# pcb.net
KiCad netlist of a schematic drawn in EAGLE
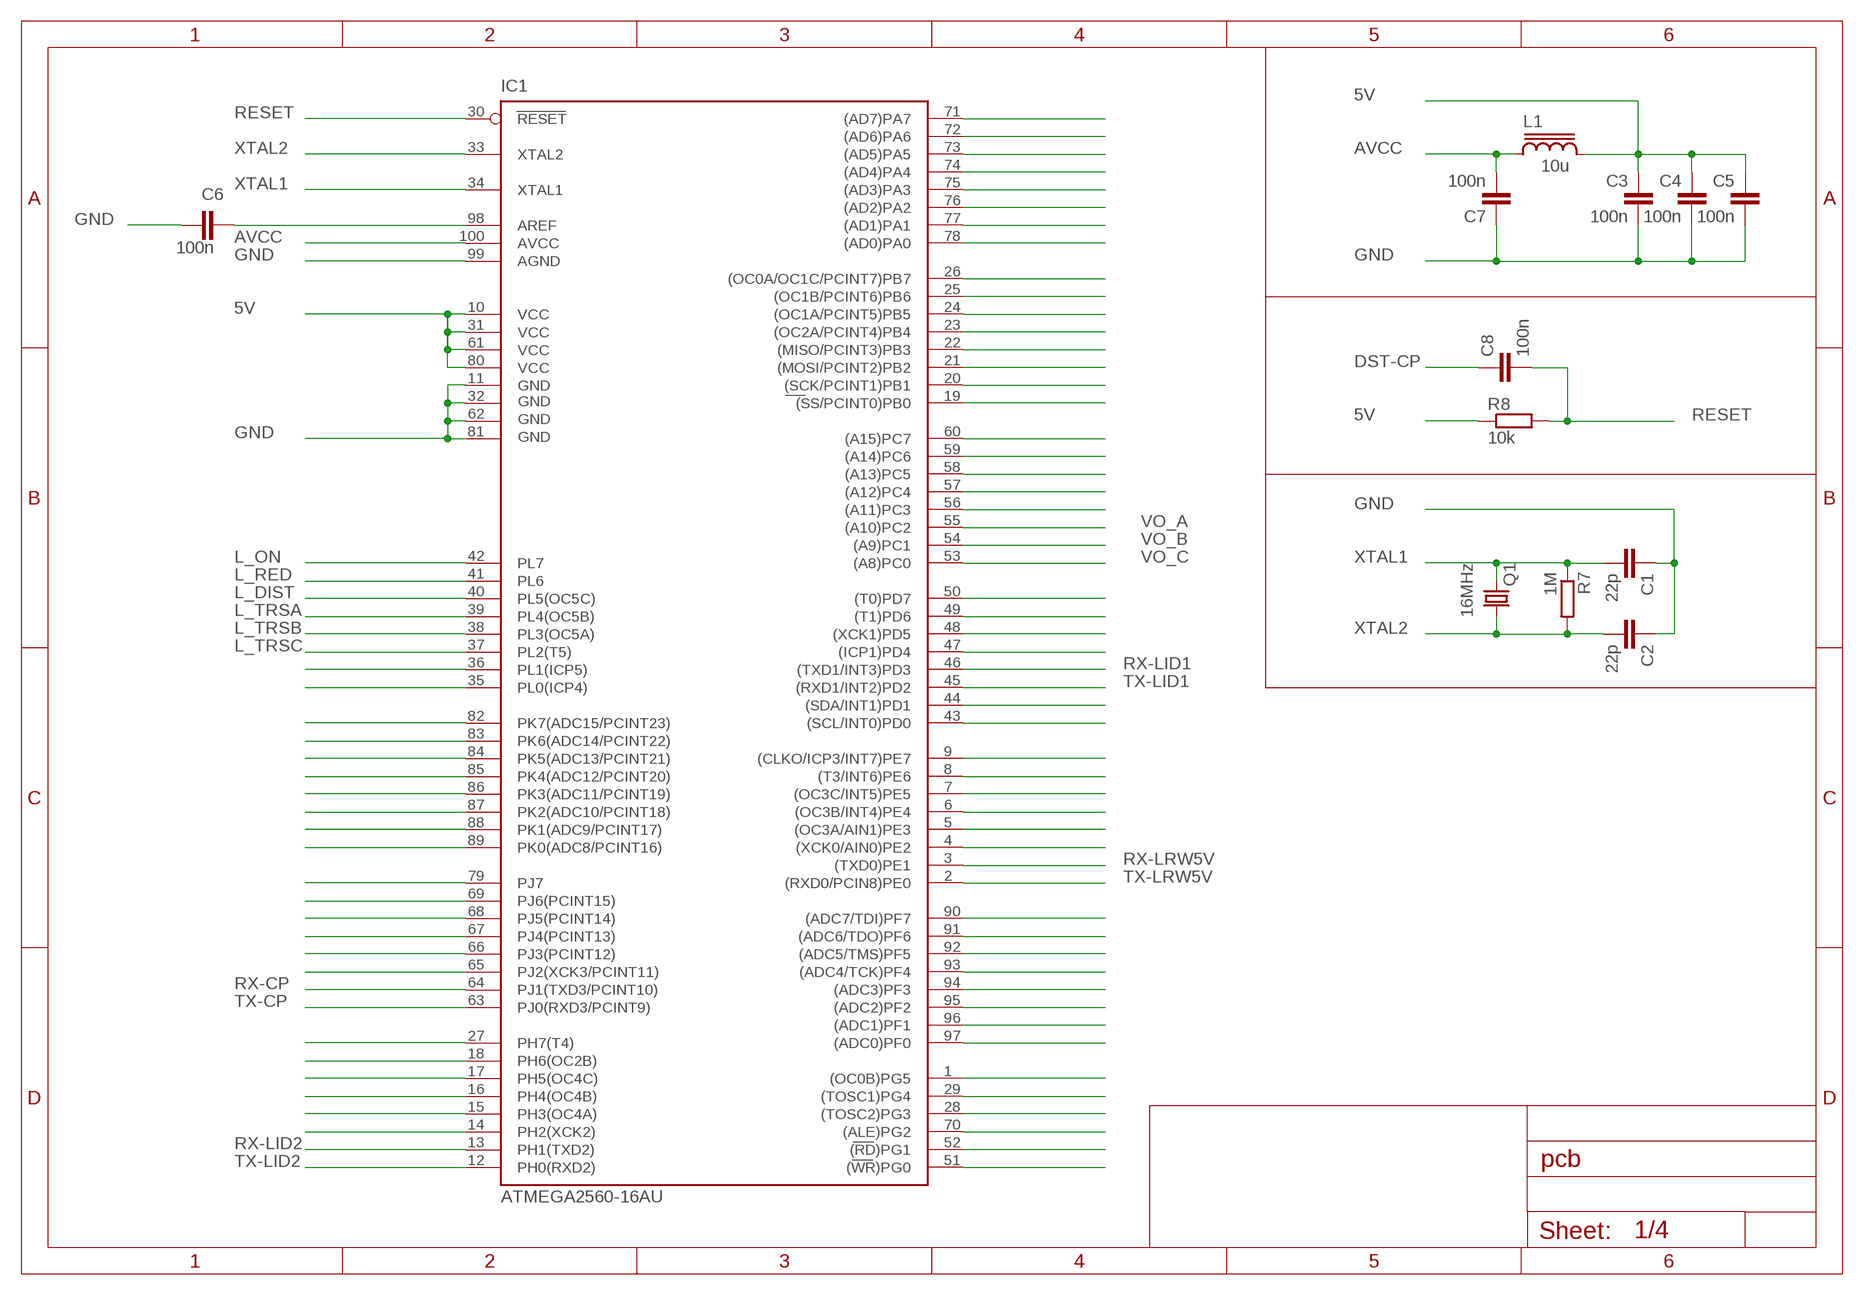
[diagram p0: schematic, sheet 1]
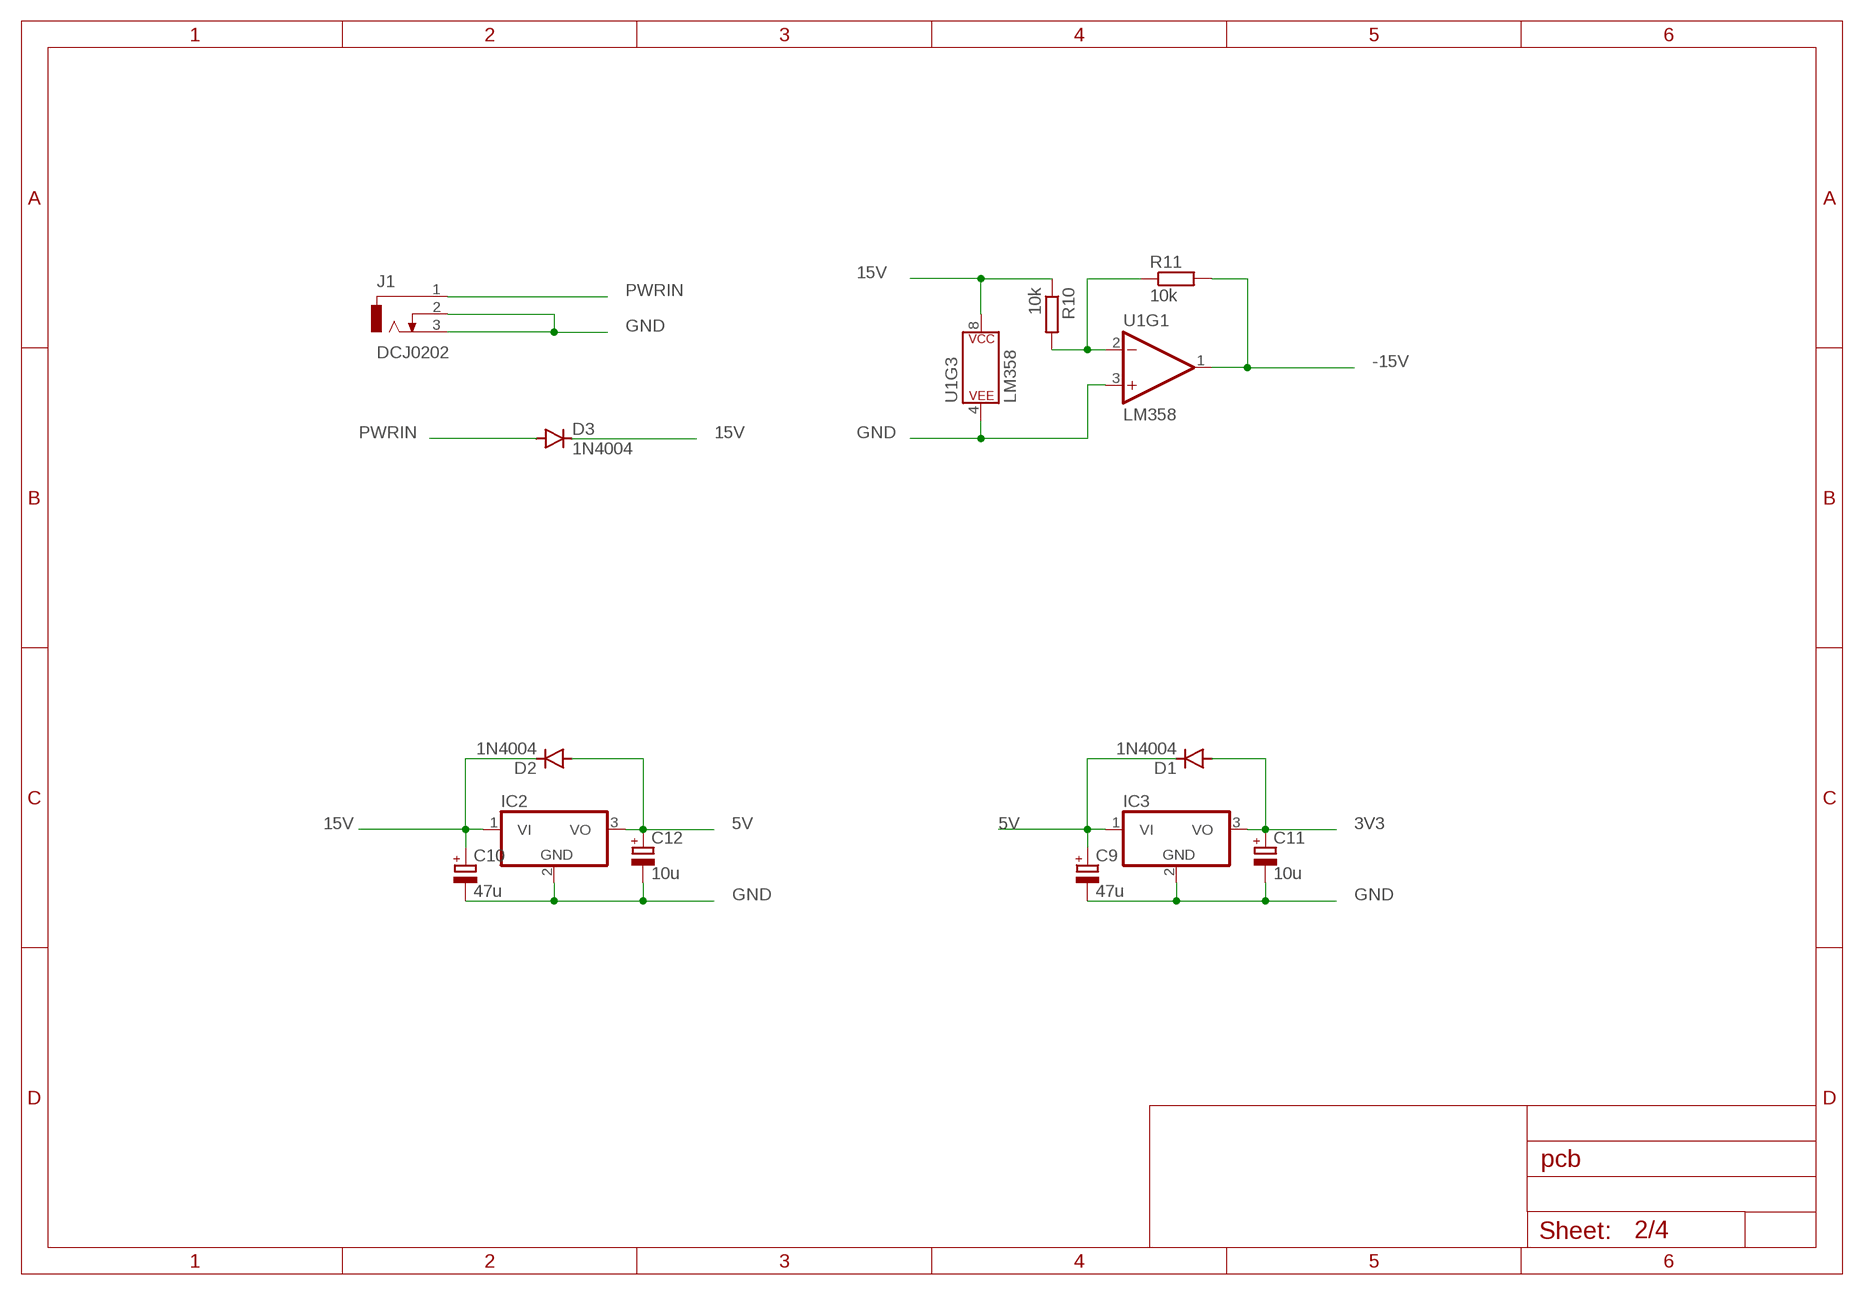
[diagram p1: schematic, sheet 2]
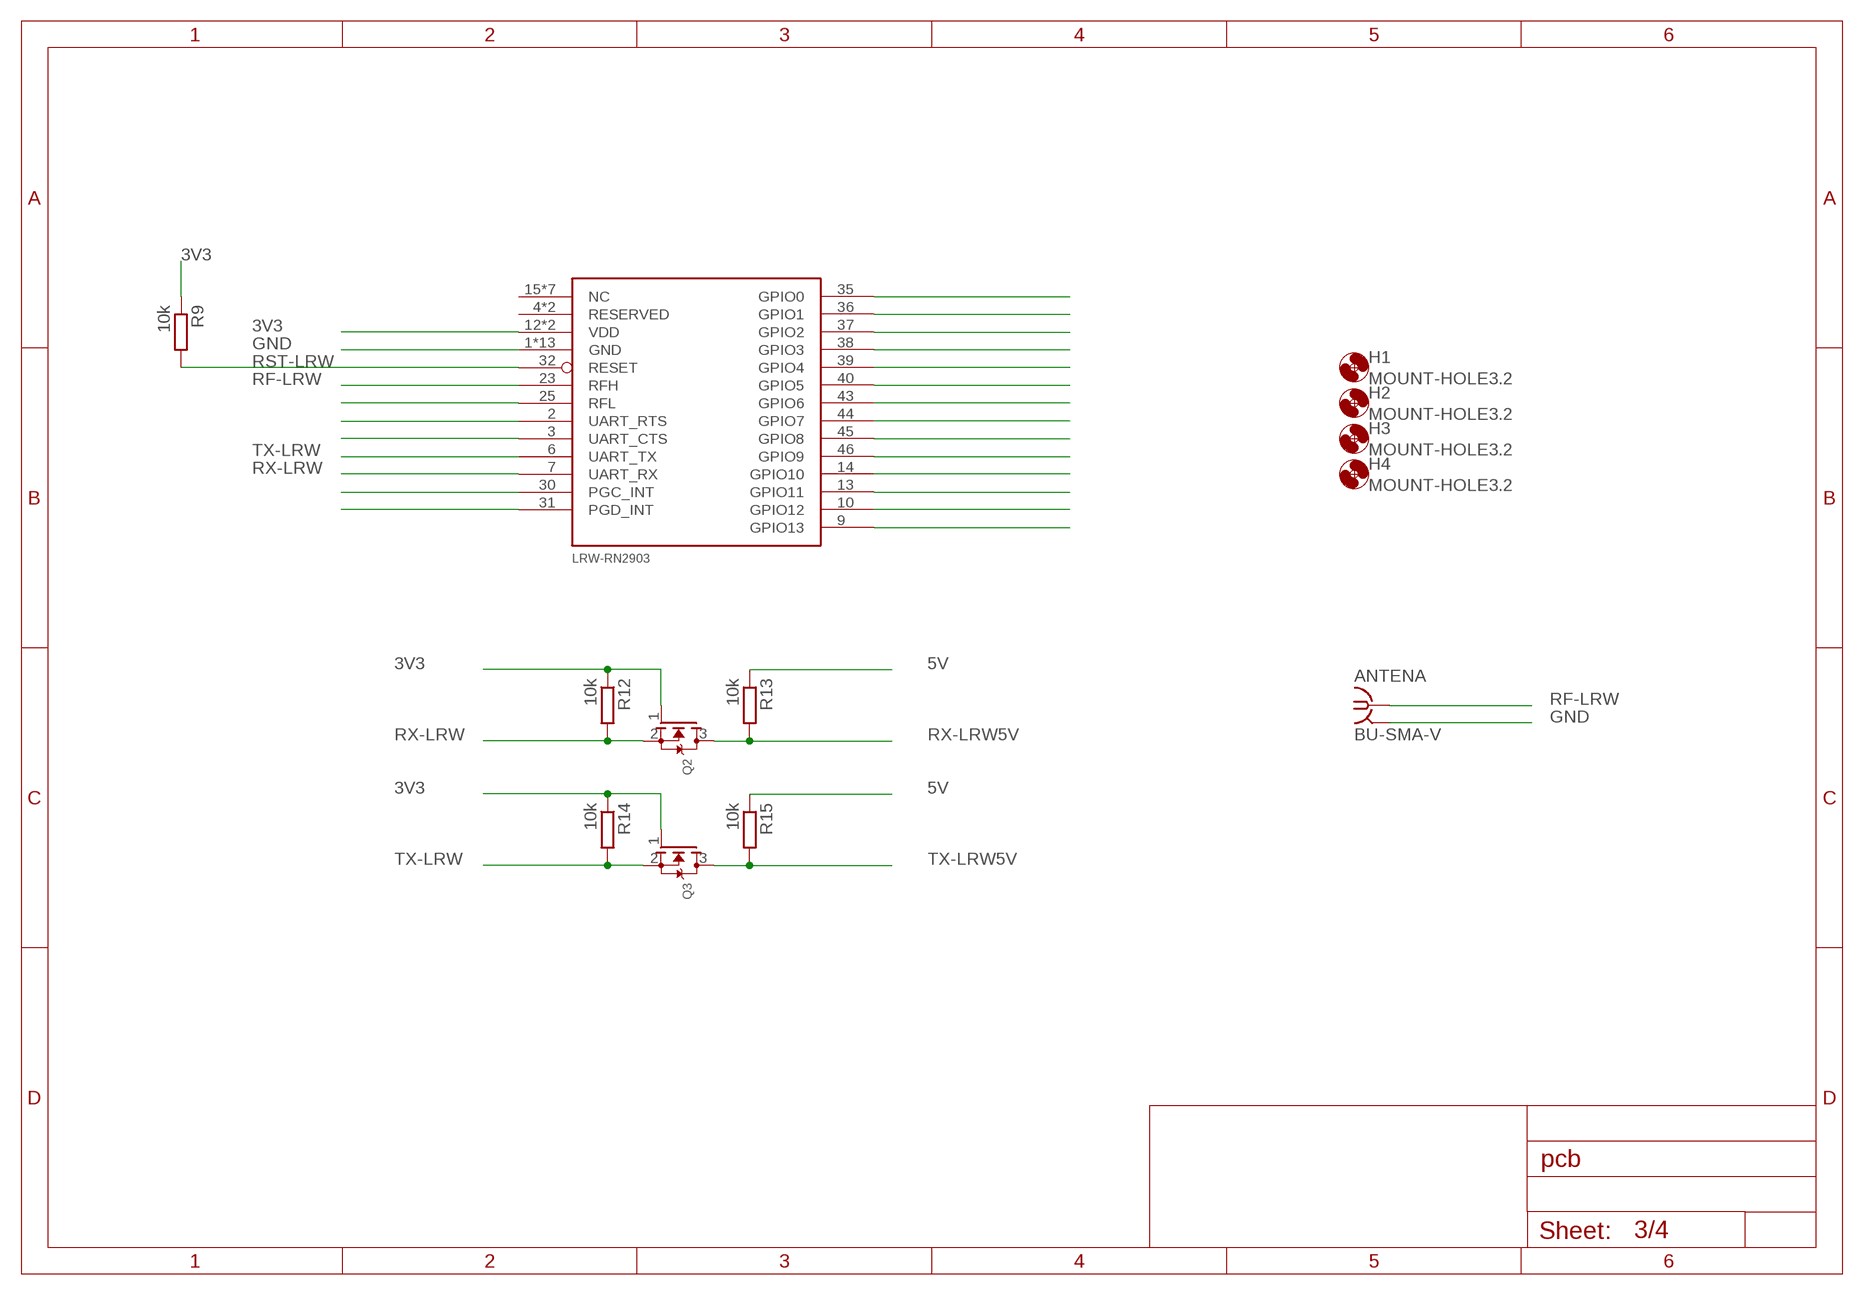
[diagram p2: schematic, sheet 3]
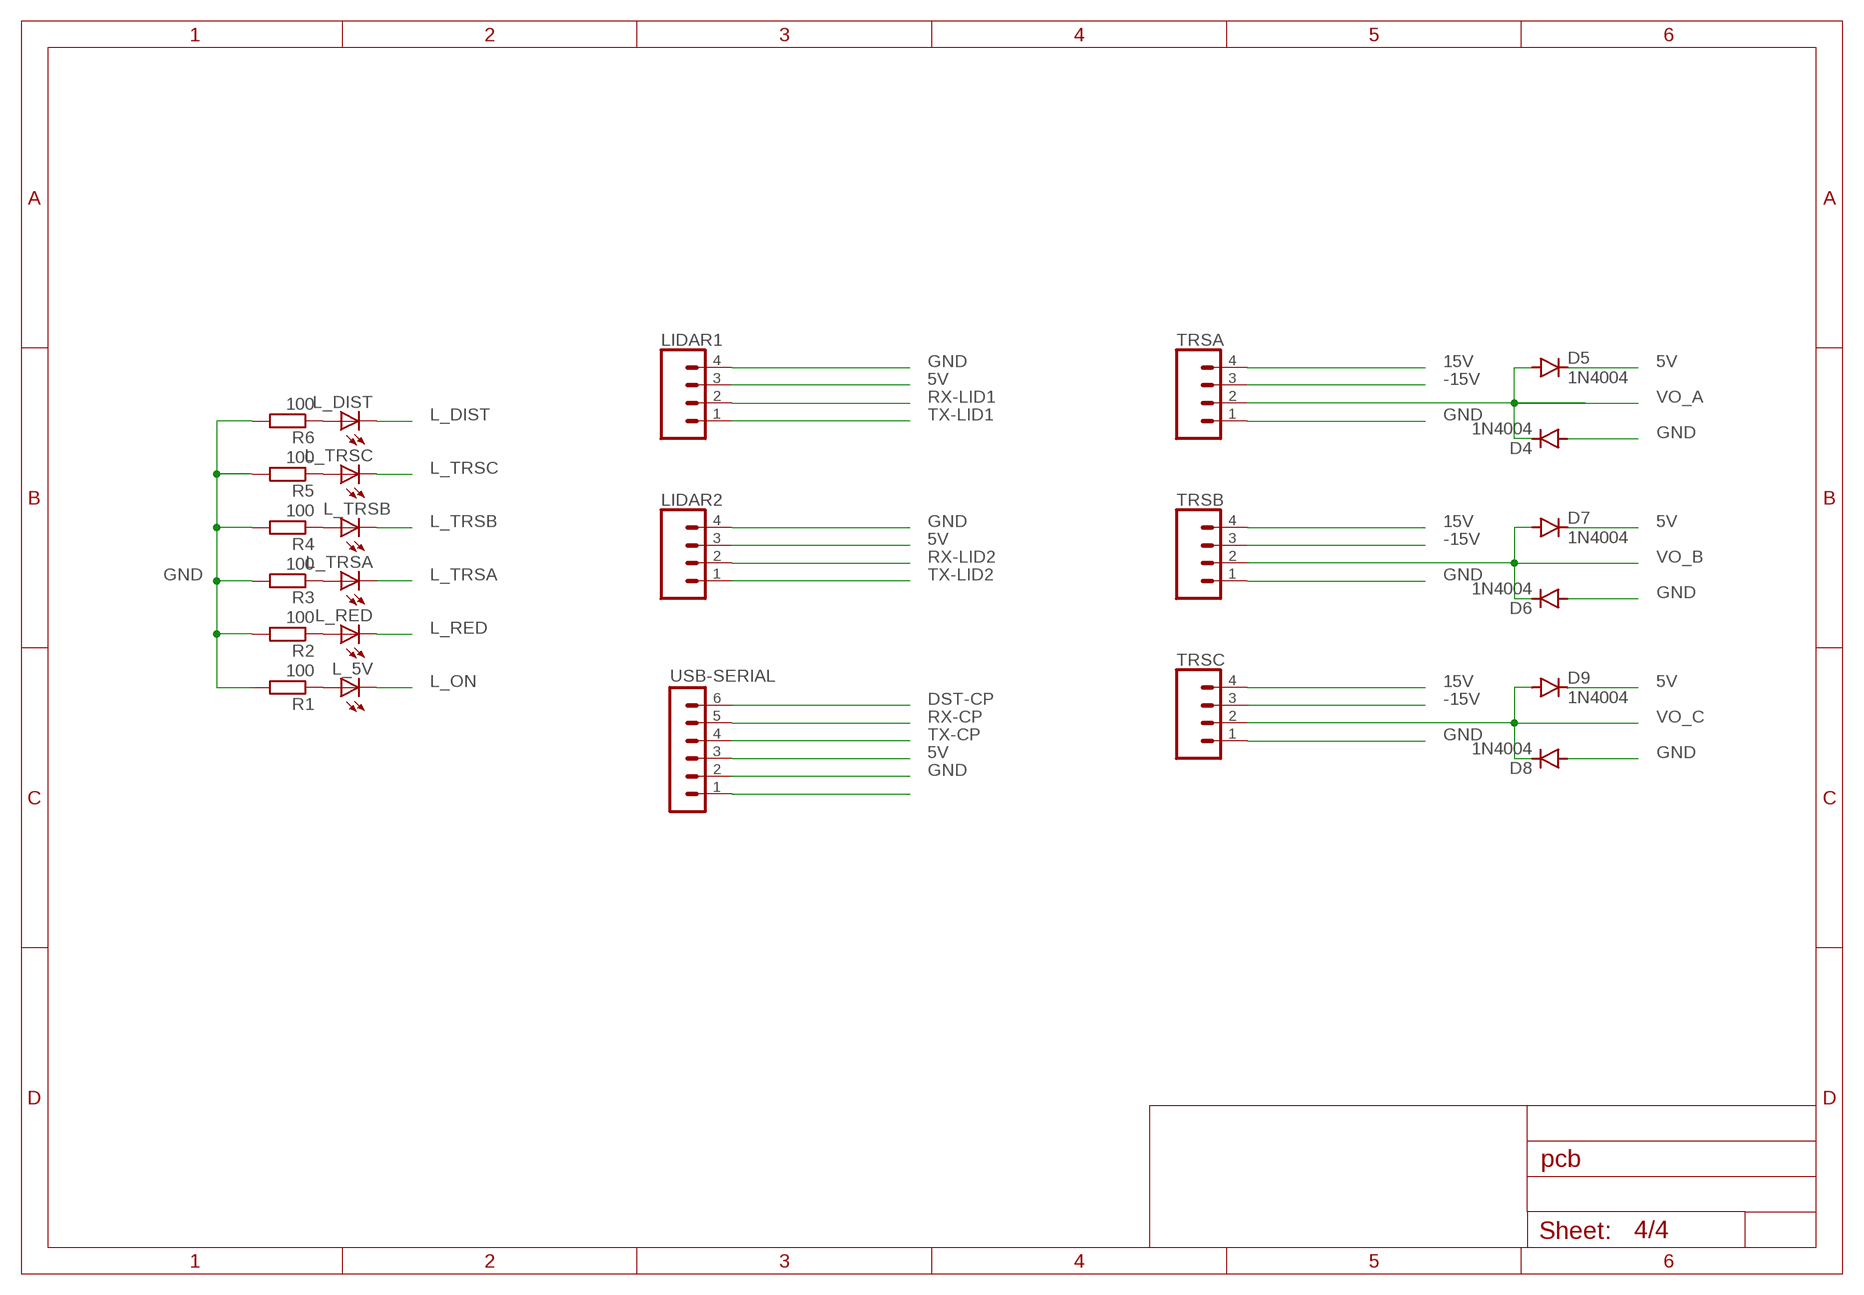
[diagram p3: schematic, sheet 4]

(export (version "E")
  (design (tool "Eeschema 10.0.6"))
  (components
    (comp (ref "D4")
      (value "1N4004")
      (footprint "eagle-import:DO41-10")
      (libsource (lib "eagle-import") (part "1N4004"))
    )
    (comp (ref "D5")
      (value "1N4004")
      (footprint "eagle-import:DO41-10")
      (libsource (lib "eagle-import") (part "1N4004"))
    )
    (comp (ref "D6")
      (value "1N4004")
      (footprint "eagle-import:DO41-10")
      (libsource (lib "eagle-import") (part "1N4004"))
    )
    (comp (ref "D7")
      (value "1N4004")
      (footprint "eagle-import:DO41-10")
      (libsource (lib "eagle-import") (part "1N4004"))
    )
    (comp (ref "D8")
      (value "1N4004")
      (footprint "eagle-import:DO41-10")
      (libsource (lib "eagle-import") (part "1N4004"))
    )
    (comp (ref "D9")
      (value "1N4004")
      (footprint "eagle-import:DO41-10")
      (libsource (lib "eagle-import") (part "1N4004"))
    )
    (comp (ref "LIDAR1")
      (value "CONN_04JST-PTH")
      (footprint "eagle-import:JST-4-PTH")
      (libsource (lib "eagle-import") (part "CONN_04JST-PTH"))
    )
    (comp (ref "LIDAR2")
      (value "CONN_04JST-PTH")
      (footprint "eagle-import:JST-4-PTH")
      (libsource (lib "eagle-import") (part "CONN_04JST-PTH"))
    )
    (comp (ref "L_5V")
      (value "LED5MM")
      (footprint "eagle-import:LED5MM")
      (libsource (lib "eagle-import") (part "LED5MM"))
    )
    (comp (ref "L_DIST")
      (value "LED5MM")
      (footprint "eagle-import:LED5MM")
      (libsource (lib "eagle-import") (part "LED5MM"))
    )
    (comp (ref "L_RED")
      (value "LED5MM")
      (footprint "eagle-import:LED5MM")
      (libsource (lib "eagle-import") (part "LED5MM"))
    )
    (comp (ref "L_TRSA")
      (value "LED5MM")
      (footprint "eagle-import:LED5MM")
      (libsource (lib "eagle-import") (part "LED5MM"))
    )
    (comp (ref "L_TRSB")
      (value "LED5MM")
      (footprint "eagle-import:LED5MM")
      (libsource (lib "eagle-import") (part "LED5MM"))
    )
    (comp (ref "L_TRSC")
      (value "LED5MM")
      (footprint "eagle-import:LED5MM")
      (libsource (lib "eagle-import") (part "LED5MM"))
    )
    (comp (ref "R1")
      (value "100")
      (footprint "eagle-import:R1206W")
      (libsource (lib "eagle-import") (part "rcl_mod_R-EU_R1206W"))
    )
    (comp (ref "R2")
      (value "100")
      (footprint "eagle-import:R1206W")
      (libsource (lib "eagle-import") (part "rcl_mod_R-EU_R1206W"))
    )
    (comp (ref "R3")
      (value "100")
      (footprint "eagle-import:R1206W")
      (libsource (lib "eagle-import") (part "rcl_mod_R-EU_R1206W"))
    )
    (comp (ref "R4")
      (value "100")
      (footprint "eagle-import:R1206W")
      (libsource (lib "eagle-import") (part "rcl_mod_R-EU_R1206W"))
    )
    (comp (ref "R5")
      (value "100")
      (footprint "eagle-import:R1206W")
      (libsource (lib "eagle-import") (part "rcl_mod_R-EU_R1206W"))
    )
    (comp (ref "R6")
      (value "100")
      (footprint "eagle-import:R1206W")
      (libsource (lib "eagle-import") (part "rcl_mod_R-EU_R1206W"))
    )
    (comp (ref "TRSA")
      (value "CONN_04JST-PTH")
      (footprint "eagle-import:JST-4-PTH")
      (libsource (lib "eagle-import") (part "CONN_04JST-PTH"))
    )
    (comp (ref "TRSB")
      (value "CONN_04JST-PTH")
      (footprint "eagle-import:JST-4-PTH")
      (libsource (lib "eagle-import") (part "CONN_04JST-PTH"))
    )
    (comp (ref "TRSC")
      (value "CONN_04JST-PTH")
      (footprint "eagle-import:JST-4-PTH")
      (libsource (lib "eagle-import") (part "CONN_04JST-PTH"))
    )
    (comp (ref "USB-SERIAL")
      (value "MA06-1")
      (footprint "eagle-import:MA06-1")
      (libsource (lib "eagle-import") (part "MA06-1"))
    )
    (comp (ref "C9")
      (value "47u")
      (footprint "eagle-import:E2,5-6E")
      (libsource (lib "eagle-import") (part "CPOL-EUE2,5-6E"))
    )
    (comp (ref "C10")
      (value "47u")
      (footprint "eagle-import:E2,5-6E")
      (libsource (lib "eagle-import") (part "CPOL-EUE2,5-6E"))
    )
    (comp (ref "C11")
      (value "10u")
      (footprint "eagle-import:E2,5-6E")
      (libsource (lib "eagle-import") (part "CPOL-EUE2,5-6E"))
    )
    (comp (ref "C12")
      (value "10u")
      (footprint "eagle-import:E2,5-6E")
      (libsource (lib "eagle-import") (part "CPOL-EUE2,5-6E"))
    )
    (comp (ref "D1")
      (value "1N4004")
      (footprint "eagle-import:DO41-10")
      (libsource (lib "eagle-import") (part "1N4004"))
    )
    (comp (ref "D2")
      (value "1N4004")
      (footprint "eagle-import:DO41-10")
      (libsource (lib "eagle-import") (part "1N4004"))
    )
    (comp (ref "D3")
      (value "1N4004")
      (footprint "eagle-import:DO41-10")
      (libsource (lib "eagle-import") (part "1N4004"))
    )
    (comp (ref "IC2")
      (value "7805T")
      (footprint "eagle-import:TO220H")
      (fields (field (name "VOUT") "5V"))
      (libsource (lib "eagle-import") (part "78T05"))
    )
    (comp (ref "IC3")
      (value "7805T")
      (footprint "eagle-import:TO220H")
      (libsource (lib "eagle-import") (part "78T05"))
    )
    (comp (ref "J1")
      (value "DCJ0202")
      (footprint "eagle-import:DCJ0202")
      (libsource (lib "eagle-import") (part "DCJ0202"))
    )
    (comp (ref "R10")
      (value "10k")
      (footprint "eagle-import:R1206W")
      (libsource (lib "eagle-import") (part "rcl_mod_R-EU_R1206W"))
    )
    (comp (ref "R11")
      (value "10k")
      (footprint "eagle-import:R1206W")
      (libsource (lib "eagle-import") (part "rcl_mod_R-EU_R1206W"))
    )
    (comp (ref "U1")
      (value "LM358")
      (footprint "eagle-import:DIP08")
      (libsource (lib "eagle-import") (part "LM358"))
    )
    (comp (ref "ANTENA")
      (value "BU-SMA-V")
      (footprint "eagle-import:BU-SMA-V")
      (libsource (lib "eagle-import") (part "BU-SMA-V"))
    )
    (comp (ref "H1")
      (value "MOUNT-HOLE3.2")
      (footprint "eagle-import:3,2")
      (libsource (lib "eagle-import") (part "MOUNT-HOLE3.2"))
    )
    (comp (ref "H2")
      (value "MOUNT-HOLE3.2")
      (footprint "eagle-import:3,2")
      (libsource (lib "eagle-import") (part "MOUNT-HOLE3.2"))
    )
    (comp (ref "H3")
      (value "MOUNT-HOLE3.2")
      (footprint "eagle-import:3,2")
      (libsource (lib "eagle-import") (part "MOUNT-HOLE3.2"))
    )
    (comp (ref "H4")
      (value "MOUNT-HOLE3.2")
      (footprint "eagle-import:3,2")
      (libsource (lib "eagle-import") (part "MOUNT-HOLE3.2"))
    )
    (comp (ref "LRW-RN2903")
      (value "MICROCHIP_RN2483")
      (footprint "eagle-import:MICROCHIP_RN2483")
      (libsource (lib "eagle-import") (part "MICROCHIP_RN2483"))
    )
    (comp (ref "Q2")
      (value "MOSFET-NWAVE")
      (footprint "eagle-import:SOT23-W")
      (libsource (lib "eagle-import") (part "MOSFET-NWAVE"))
    )
    (comp (ref "Q3")
      (value "MOSFET-NWAVE")
      (footprint "eagle-import:SOT23-W")
      (libsource (lib "eagle-import") (part "MOSFET-NWAVE"))
    )
    (comp (ref "R9")
      (value "10k")
      (footprint "eagle-import:R1206W")
      (libsource (lib "eagle-import") (part "R-EU_R1206W"))
    )
    (comp (ref "R12")
      (value "10k")
      (footprint "eagle-import:R1206W")
      (libsource (lib "eagle-import") (part "rcl_mod_R-EU_R1206W"))
    )
    (comp (ref "R13")
      (value "10k")
      (footprint "eagle-import:R1206W")
      (libsource (lib "eagle-import") (part "rcl_mod_R-EU_R1206W"))
    )
    (comp (ref "R14")
      (value "10k")
      (footprint "eagle-import:R1206W")
      (libsource (lib "eagle-import") (part "rcl_mod_R-EU_R1206W"))
    )
    (comp (ref "R15")
      (value "10k")
      (footprint "eagle-import:R1206W")
      (libsource (lib "eagle-import") (part "rcl_mod_R-EU_R1206W"))
    )
    (comp (ref "C1")
      (value "22p")
      (footprint "eagle-import:C050-025X075")
      (libsource (lib "eagle-import") (part "C-EU050-025X075"))
    )
    (comp (ref "C2")
      (value "22p")
      (footprint "eagle-import:C050-025X075")
      (libsource (lib "eagle-import") (part "C-EU050-025X075"))
    )
    (comp (ref "C3")
      (value "100n")
      (footprint "eagle-import:C050-025X075")
      (libsource (lib "eagle-import") (part "C-EU050-025X075"))
    )
    (comp (ref "C4")
      (value "100n")
      (footprint "eagle-import:C050-025X075")
      (libsource (lib "eagle-import") (part "C-EU050-025X075"))
    )
    (comp (ref "C5")
      (value "100n")
      (footprint "eagle-import:C050-025X075")
      (libsource (lib "eagle-import") (part "C-EU050-025X075"))
    )
    (comp (ref "C6")
      (value "100n")
      (footprint "eagle-import:C050-025X075")
      (libsource (lib "eagle-import") (part "C-EU050-025X075"))
    )
    (comp (ref "C7")
      (value "100n")
      (footprint "eagle-import:C050-025X075")
      (libsource (lib "eagle-import") (part "C-EU050-025X075"))
    )
    (comp (ref "C8")
      (value "100n")
      (footprint "eagle-import:C050-025X075")
      (libsource (lib "eagle-import") (part "C-EU050-025X075"))
    )
    (comp (ref "IC1")
      (value "ATMEGA2560-16AU")
      (footprint "eagle-import:TQFP100")
      (libsource (lib "eagle-import") (part "ATMEGAAU2560-16"))
    )
    (comp (ref "L1")
      (value "10u")
      (footprint "eagle-import:MSS1260")
      (libsource (lib "eagle-import") (part "MSS1260"))
    )
    (comp (ref "Q1")
      (value "16MHz")
      (footprint "eagle-import:HC18U-V")
      (libsource (lib "eagle-import") (part "CRYSTALHC18U-V"))
    )
    (comp (ref "R7")
      (value "1M")
      (footprint "eagle-import:R1206W")
      (libsource (lib "eagle-import") (part "R-EU_R1206W"))
    )
    (comp (ref "R8")
      (value "10k")
      (footprint "eagle-import:R1206W")
      (libsource (lib "eagle-import") (part "rcl_mod_R-EU_R1206W"))
    )
  )
  (nets
    (net (code "1") (name "-15V") (class "Default")
      (node (ref "R11") (pin "2") (pinfunction "2_2") (pintype "passive"))
      (node (ref "TRSA") (pin "3") (pinfunction "3_3") (pintype "passive"))
      (node (ref "TRSB") (pin "3") (pinfunction "3_3") (pintype "passive"))
      (node (ref "TRSC") (pin "3") (pinfunction "3_3") (pintype "passive"))
      (node (ref "U1") (pin "1") (pinfunction "OUT_1") (pintype "output"))
    )
    (net (code "2") (name "3V3") (class "Default")
      (node (ref "C11") (pin "+") (pinfunction "+_+") (pintype "passive"))
      (node (ref "D1") (pin "A") (pinfunction "A_A") (pintype "passive"))
      (node (ref "IC3") (pin "3") (pinfunction "VO_3") (pintype "passive"))
      (node (ref "LRW-RN2903") (pin "12") (pinfunction "VDD_12") (pintype "power_in"))
      (node (ref "LRW-RN2903") (pin "34") (pinfunction "VDD_34") (pintype "power_in"))
      (node (ref "Q2") (pin "1") (pinfunction "G_1") (pintype "bidirectional"))
      (node (ref "Q3") (pin "1") (pinfunction "G_1") (pintype "bidirectional"))
      (node (ref "R12") (pin "1") (pinfunction "1_1") (pintype "passive"))
      (node (ref "R14") (pin "1") (pinfunction "1_1") (pintype "passive"))
      (node (ref "R9") (pin "1") (pinfunction "1_1") (pintype "passive"))
    )
    (net (code "3") (name "5V") (class "Default")
      (node (ref "C12") (pin "+") (pinfunction "+_+") (pintype "passive"))
      (node (ref "C3") (pin "2") (pinfunction "2_2") (pintype "passive"))
      (node (ref "C4") (pin "2") (pinfunction "2_2") (pintype "passive"))
      (node (ref "C5") (pin "2") (pinfunction "2_2") (pintype "passive"))
      (node (ref "C9") (pin "+") (pinfunction "+_+") (pintype "passive"))
      (node (ref "D1") (pin "C") (pinfunction "C_C") (pintype "passive"))
      (node (ref "D2") (pin "A") (pinfunction "A_A") (pintype "passive"))
      (node (ref "D5") (pin "C") (pinfunction "C_C") (pintype "passive"))
      (node (ref "D7") (pin "C") (pinfunction "C_C") (pintype "passive"))
      (node (ref "D9") (pin "C") (pinfunction "C_C") (pintype "passive"))
      (node (ref "IC1") (pin "10") (pinfunction "VCC_10") (pintype "power_in"))
      (node (ref "IC1") (pin "31") (pinfunction "VCC1_31") (pintype "power_in"))
      (node (ref "IC1") (pin "61") (pinfunction "VCC2_61") (pintype "power_in"))
      (node (ref "IC1") (pin "80") (pinfunction "VCC3_80") (pintype "power_in"))
      (node (ref "IC2") (pin "3") (pinfunction "VO_3") (pintype "passive"))
      (node (ref "IC3") (pin "1") (pinfunction "VI_1") (pintype "input"))
      (node (ref "L1") (pin "2") (pinfunction "2_2") (pintype "passive"))
      (node (ref "LIDAR1") (pin "3") (pinfunction "3_3") (pintype "passive"))
      (node (ref "LIDAR2") (pin "3") (pinfunction "3_3") (pintype "passive"))
      (node (ref "R13") (pin "1") (pinfunction "1_1") (pintype "passive"))
      (node (ref "R15") (pin "1") (pinfunction "1_1") (pintype "passive"))
      (node (ref "R8") (pin "1") (pinfunction "1_1") (pintype "passive"))
      (node (ref "USB-SERIAL") (pin "3") (pinfunction "3_3") (pintype "passive"))
    )
    (net (code "4") (name "15V") (class "Default")
      (node (ref "C10") (pin "+") (pinfunction "+_+") (pintype "passive"))
      (node (ref "D2") (pin "C") (pinfunction "C_C") (pintype "passive"))
      (node (ref "D3") (pin "C") (pinfunction "C_C") (pintype "passive"))
      (node (ref "IC2") (pin "1") (pinfunction "VI_1") (pintype "input"))
      (node (ref "R10") (pin "1") (pinfunction "1_1") (pintype "passive"))
      (node (ref "TRSA") (pin "4") (pinfunction "4_4") (pintype "passive"))
      (node (ref "TRSB") (pin "4") (pinfunction "4_4") (pintype "passive"))
      (node (ref "TRSC") (pin "4") (pinfunction "4_4") (pintype "passive"))
      (node (ref "U1") (pin "8") (pinfunction "P$V+_8") (pintype "bidirectional"))
    )
    (net (code "5") (name "AVCC") (class "Default")
      (node (ref "C7") (pin "2") (pinfunction "2_2") (pintype "passive"))
      (node (ref "IC1") (pin "100") (pinfunction "AVCC_100") (pintype "power_in"))
      (node (ref "L1") (pin "1") (pinfunction "1_1") (pintype "passive"))
    )
    (net (code "6") (name "DST-CP") (class "Default")
      (node (ref "C8") (pin "1") (pinfunction "1_1") (pintype "passive"))
      (node (ref "USB-SERIAL") (pin "6") (pinfunction "6_6") (pintype "passive"))
    )
    (net (code "7") (name "GND") (class "Default")
      (node (ref "ANTENA") (pin "2") (pinfunction "2_2") (pintype "passive"))
      (node (ref "ANTENA") (pin "3") (pinfunction "2_3") (pintype "passive"))
      (node (ref "ANTENA") (pin "4") (pinfunction "2_4") (pintype "passive"))
      (node (ref "ANTENA") (pin "5") (pinfunction "2_5") (pintype "passive"))
      (node (ref "C1") (pin "1") (pinfunction "1_1") (pintype "passive"))
      (node (ref "C10") (pin "-") (pinfunction "-_-") (pintype "passive"))
      (node (ref "C11") (pin "-") (pinfunction "-_-") (pintype "passive"))
      (node (ref "C12") (pin "-") (pinfunction "-_-") (pintype "passive"))
      (node (ref "C2") (pin "1") (pinfunction "1_1") (pintype "passive"))
      (node (ref "C3") (pin "1") (pinfunction "1_1") (pintype "passive"))
      (node (ref "C4") (pin "1") (pinfunction "1_1") (pintype "passive"))
      (node (ref "C5") (pin "1") (pinfunction "1_1") (pintype "passive"))
      (node (ref "C6") (pin "2") (pinfunction "2_2") (pintype "passive"))
      (node (ref "C7") (pin "1") (pinfunction "1_1") (pintype "passive"))
      (node (ref "C9") (pin "-") (pinfunction "-_-") (pintype "passive"))
      (node (ref "D4") (pin "A") (pinfunction "A_A") (pintype "passive"))
      (node (ref "D6") (pin "A") (pinfunction "A_A") (pintype "passive"))
      (node (ref "D8") (pin "A") (pinfunction "A_A") (pintype "passive"))
      (node (ref "IC1") (pin "11") (pinfunction "GND_11") (pintype "power_in"))
      (node (ref "IC1") (pin "32") (pinfunction "GND1_32") (pintype "power_in"))
      (node (ref "IC1") (pin "62") (pinfunction "GND2_62") (pintype "power_in"))
      (node (ref "IC1") (pin "81") (pinfunction "GND3_81") (pintype "power_in"))
      (node (ref "IC1") (pin "99") (pinfunction "AGND_99") (pintype "power_in"))
      (node (ref "IC2") (pin "2") (pinfunction "GND_2") (pintype "passive"))
      (node (ref "IC3") (pin "2") (pinfunction "GND_2") (pintype "passive"))
      (node (ref "J1") (pin "2") (pinfunction "2_2") (pintype "passive"))
      (node (ref "J1") (pin "3") (pinfunction "3_3") (pintype "passive"))
      (node (ref "LIDAR1") (pin "4") (pinfunction "4_4") (pintype "passive"))
      (node (ref "LIDAR2") (pin "4") (pinfunction "4_4") (pintype "passive"))
      (node (ref "LRW-RN2903") (pin "1") (pinfunction "GND_1") (pintype "power_in"))
      (node (ref "LRW-RN2903") (pin "11") (pinfunction "GND_11") (pintype "power_in"))
      (node (ref "LRW-RN2903") (pin "20") (pinfunction "GND_20") (pintype "power_in"))
      (node (ref "LRW-RN2903") (pin "21") (pinfunction "GND_21") (pintype "power_in"))
      (node (ref "LRW-RN2903") (pin "22") (pinfunction "GND_22") (pintype "power_in"))
      (node (ref "LRW-RN2903") (pin "24") (pinfunction "GND_24") (pintype "power_in"))
      (node (ref "LRW-RN2903") (pin "26") (pinfunction "GND_26") (pintype "power_in"))
      (node (ref "LRW-RN2903") (pin "27") (pinfunction "GND_27") (pintype "power_in"))
      (node (ref "LRW-RN2903") (pin "28") (pinfunction "GND_28") (pintype "power_in"))
      (node (ref "LRW-RN2903") (pin "33") (pinfunction "GND_33") (pintype "power_in"))
      (node (ref "LRW-RN2903") (pin "41") (pinfunction "GND_41") (pintype "power_in"))
      (node (ref "LRW-RN2903") (pin "47") (pinfunction "GND_47") (pintype "power_in"))
      (node (ref "LRW-RN2903") (pin "8") (pinfunction "GND_8") (pintype "power_in"))
      (node (ref "R1") (pin "2") (pinfunction "2_2") (pintype "passive"))
      (node (ref "R2") (pin "2") (pinfunction "2_2") (pintype "passive"))
      (node (ref "R3") (pin "2") (pinfunction "2_2") (pintype "passive"))
      (node (ref "R4") (pin "2") (pinfunction "2_2") (pintype "passive"))
      (node (ref "R5") (pin "2") (pinfunction "2_2") (pintype "passive"))
      (node (ref "R6") (pin "2") (pinfunction "2_2") (pintype "passive"))
      (node (ref "TRSA") (pin "1") (pinfunction "1_1") (pintype "passive"))
      (node (ref "TRSB") (pin "1") (pinfunction "1_1") (pintype "passive"))
      (node (ref "TRSC") (pin "1") (pinfunction "1_1") (pintype "passive"))
      (node (ref "U1") (pin "3") (pinfunction "+IN_3") (pintype "input"))
      (node (ref "U1") (pin "4") (pinfunction "P$V-_4") (pintype "bidirectional"))
      (node (ref "USB-SERIAL") (pin "2") (pinfunction "2_2") (pintype "passive"))
    )
    (net (code "8") (name "L_DIST") (class "Default")
      (node (ref "IC1") (pin "40") (pinfunction "PL5(OC5C)_40") (pintype "bidirectional"))
      (node (ref "L_DIST") (pin "K") (pinfunction "C_K") (pintype "passive"))
    )
    (net (code "9") (name "L_ON") (class "Default")
      (node (ref "IC1") (pin "42") (pinfunction "PL7_42") (pintype "bidirectional"))
      (node (ref "L_5V") (pin "K") (pinfunction "C_K") (pintype "passive"))
    )
    (net (code "10") (name "L_RED") (class "Default")
      (node (ref "IC1") (pin "41") (pinfunction "PL6_41") (pintype "bidirectional"))
      (node (ref "L_RED") (pin "K") (pinfunction "C_K") (pintype "passive"))
    )
    (net (code "11") (name "L_TRSA") (class "Default")
      (node (ref "IC1") (pin "39") (pinfunction "PL4(OC5B)_39") (pintype "bidirectional"))
      (node (ref "L_TRSA") (pin "K") (pinfunction "C_K") (pintype "passive"))
    )
    (net (code "12") (name "L_TRSB") (class "Default")
      (node (ref "IC1") (pin "38") (pinfunction "PL3(OC5A)_38") (pintype "bidirectional"))
      (node (ref "L_TRSB") (pin "K") (pinfunction "C_K") (pintype "passive"))
    )
    (net (code "13") (name "L_TRSC") (class "Default")
      (node (ref "IC1") (pin "37") (pinfunction "PL2(T5)_37") (pintype "bidirectional"))
      (node (ref "L_TRSC") (pin "K") (pinfunction "C_K") (pintype "passive"))
    )
    (net (code "14") (name "Net-(IC1-AREF)") (class "Default")
      (node (ref "C6") (pin "1") (pinfunction "1_1") (pintype "passive"))
      (node (ref "IC1") (pin "98") (pinfunction "AREF_98") (pintype "bidirectional"))
    )
    (net (code "15") (name "Net-(L_5V-PadA)") (class "Default")
      (node (ref "L_5V") (pin "A") (pinfunction "A_A") (pintype "passive"))
      (node (ref "R1") (pin "1") (pinfunction "1_1") (pintype "passive"))
    )
    (net (code "16") (name "Net-(L_DIST-PadA)") (class "Default")
      (node (ref "L_DIST") (pin "A") (pinfunction "A_A") (pintype "passive"))
      (node (ref "R6") (pin "1") (pinfunction "1_1") (pintype "passive"))
    )
    (net (code "17") (name "Net-(L_RED-PadA)") (class "Default")
      (node (ref "L_RED") (pin "A") (pinfunction "A_A") (pintype "passive"))
      (node (ref "R2") (pin "1") (pinfunction "1_1") (pintype "passive"))
    )
    (net (code "18") (name "Net-(L_TRSA-PadA)") (class "Default")
      (node (ref "L_TRSA") (pin "A") (pinfunction "A_A") (pintype "passive"))
      (node (ref "R3") (pin "1") (pinfunction "1_1") (pintype "passive"))
    )
    (net (code "19") (name "Net-(L_TRSB-PadA)") (class "Default")
      (node (ref "L_TRSB") (pin "A") (pinfunction "A_A") (pintype "passive"))
      (node (ref "R4") (pin "1") (pinfunction "1_1") (pintype "passive"))
    )
    (net (code "20") (name "Net-(L_TRSC-PadA)") (class "Default")
      (node (ref "L_TRSC") (pin "A") (pinfunction "A_A") (pintype "passive"))
      (node (ref "R5") (pin "1") (pinfunction "1_1") (pintype "passive"))
    )
    (net (code "21") (name "Net-(U1A--IN)") (class "Default")
      (node (ref "R10") (pin "2") (pinfunction "2_2") (pintype "passive"))
      (node (ref "R11") (pin "1") (pinfunction "1_1") (pintype "passive"))
      (node (ref "U1") (pin "2") (pinfunction "-IN_2") (pintype "input"))
    )
    (net (code "22") (name "PWRIN") (class "Default")
      (node (ref "D3") (pin "A") (pinfunction "A_A") (pintype "passive"))
      (node (ref "J1") (pin "1") (pinfunction "1_1") (pintype "passive"))
    )
    (net (code "23") (name "RESET") (class "Default")
      (node (ref "C8") (pin "2") (pinfunction "2_2") (pintype "passive"))
      (node (ref "IC1") (pin "30") (pinfunction "RESET_30") (pintype "input"))
      (node (ref "R8") (pin "2") (pinfunction "2_2") (pintype "passive"))
    )
    (net (code "24") (name "RF-LRW") (class "Default")
      (node (ref "ANTENA") (pin "1") (pinfunction "1_1") (pintype "passive"))
      (node (ref "LRW-RN2903") (pin "23") (pinfunction "RFH_23") (pintype "bidirectional"))
    )
    (net (code "25") (name "RST-LRW") (class "Default")
      (node (ref "LRW-RN2903") (pin "32") (pinfunction "RESET_32") (pintype "input"))
      (node (ref "R9") (pin "2") (pinfunction "2_2") (pintype "passive"))
    )
    (net (code "26") (name "RX-CP") (class "Default")
      (node (ref "IC1") (pin "64") (pinfunction "PJ1(TXD3/PCINT10)_64") (pintype "bidirectional"))
      (node (ref "USB-SERIAL") (pin "5") (pinfunction "5_5") (pintype "passive"))
    )
    (net (code "27") (name "RX-LID1") (class "Default")
      (node (ref "IC1") (pin "46") (pinfunction "(TXD1/INT3)PD3_46") (pintype "bidirectional"))
      (node (ref "LIDAR1") (pin "2") (pinfunction "2_2") (pintype "passive"))
    )
    (net (code "28") (name "RX-LID2") (class "Default")
      (node (ref "IC1") (pin "13") (pinfunction "PH1(TXD2)_13") (pintype "bidirectional"))
      (node (ref "LIDAR2") (pin "2") (pinfunction "2_2") (pintype "passive"))
    )
    (net (code "29") (name "RX-LRW") (class "Default")
      (node (ref "LRW-RN2903") (pin "7") (pinfunction "UART_RX_7") (pintype "input"))
      (node (ref "Q2") (pin "2") (pinfunction "S_2") (pintype "bidirectional"))
      (node (ref "R12") (pin "2") (pinfunction "2_2") (pintype "passive"))
    )
    (net (code "30") (name "RX-LRW5V") (class "Default")
      (node (ref "IC1") (pin "3") (pinfunction "(TXD0)PE1_3") (pintype "bidirectional"))
      (node (ref "Q2") (pin "3") (pinfunction "D_3") (pintype "bidirectional"))
      (node (ref "R13") (pin "2") (pinfunction "2_2") (pintype "passive"))
    )
    (net (code "31") (name "TX-CP") (class "Default")
      (node (ref "IC1") (pin "63") (pinfunction "PJ0(RXD3/PCINT9)_63") (pintype "bidirectional"))
      (node (ref "USB-SERIAL") (pin "4") (pinfunction "4_4") (pintype "passive"))
    )
    (net (code "32") (name "TX-LID1") (class "Default")
      (node (ref "IC1") (pin "45") (pinfunction "(RXD1/INT2)PD2_45") (pintype "bidirectional"))
      (node (ref "LIDAR1") (pin "1") (pinfunction "1_1") (pintype "passive"))
    )
    (net (code "33") (name "TX-LID2") (class "Default")
      (node (ref "IC1") (pin "12") (pinfunction "PH0(RXD2)_12") (pintype "bidirectional"))
      (node (ref "LIDAR2") (pin "1") (pinfunction "1_1") (pintype "passive"))
    )
    (net (code "34") (name "TX-LRW") (class "Default")
      (node (ref "LRW-RN2903") (pin "6") (pinfunction "UART_TX_6") (pintype "output"))
      (node (ref "Q3") (pin "2") (pinfunction "S_2") (pintype "bidirectional"))
      (node (ref "R14") (pin "2") (pinfunction "2_2") (pintype "passive"))
    )
    (net (code "35") (name "TX-LRW5V") (class "Default")
      (node (ref "IC1") (pin "2") (pinfunction "(RXD0/PCIN8)PE0_2") (pintype "bidirectional"))
      (node (ref "Q3") (pin "3") (pinfunction "D_3") (pintype "bidirectional"))
      (node (ref "R15") (pin "2") (pinfunction "2_2") (pintype "passive"))
    )
    (net (code "36") (name "VO_A") (class "Default")
      (node (ref "D4") (pin "C") (pinfunction "C_C") (pintype "passive"))
      (node (ref "D5") (pin "A") (pinfunction "A_A") (pintype "passive"))
      (node (ref "IC1") (pin "55") (pinfunction "(A10)PC2_55") (pintype "bidirectional"))
      (node (ref "TRSA") (pin "2") (pinfunction "2_2") (pintype "passive"))
    )
    (net (code "37") (name "VO_B") (class "Default")
      (node (ref "D6") (pin "C") (pinfunction "C_C") (pintype "passive"))
      (node (ref "D7") (pin "A") (pinfunction "A_A") (pintype "passive"))
      (node (ref "IC1") (pin "54") (pinfunction "(A9)PC1_54") (pintype "bidirectional"))
      (node (ref "TRSB") (pin "2") (pinfunction "2_2") (pintype "passive"))
    )
    (net (code "38") (name "VO_C") (class "Default")
      (node (ref "D8") (pin "C") (pinfunction "C_C") (pintype "passive"))
      (node (ref "D9") (pin "A") (pinfunction "A_A") (pintype "passive"))
      (node (ref "IC1") (pin "53") (pinfunction "(A8)PC0_53") (pintype "bidirectional"))
      (node (ref "TRSC") (pin "2") (pinfunction "2_2") (pintype "passive"))
    )
    (net (code "39") (name "XTAL1") (class "Default")
      (node (ref "C1") (pin "2") (pinfunction "2_2") (pintype "passive"))
      (node (ref "IC1") (pin "34") (pinfunction "XTAL1_34") (pintype "input"))
      (node (ref "Q1") (pin "1") (pinfunction "1_1") (pintype "passive"))
      (node (ref "R7") (pin "1") (pinfunction "1_1") (pintype "passive"))
    )
    (net (code "40") (name "XTAL2") (class "Default")
      (node (ref "C2") (pin "2") (pinfunction "2_2") (pintype "passive"))
      (node (ref "IC1") (pin "33") (pinfunction "XTAL2_33") (pintype "output"))
      (node (ref "Q1") (pin "2") (pinfunction "2_2") (pintype "passive"))
      (node (ref "R7") (pin "2") (pinfunction "2_2") (pintype "passive"))
    )
    (net (code "41") (name "unconnected-(IC1-(A11)PC3-Pad56)") (class "Default")
      (node (ref "IC1") (pin "56") (pinfunction "(A11)PC3_56") (pintype "bidirectional"))
    )
    (net (code "42") (name "unconnected-(IC1-(A12)PC4-Pad57)") (class "Default")
      (node (ref "IC1") (pin "57") (pinfunction "(A12)PC4_57") (pintype "bidirectional"))
    )
    (net (code "43") (name "unconnected-(IC1-(A13)PC5-Pad58)") (class "Default")
      (node (ref "IC1") (pin "58") (pinfunction "(A13)PC5_58") (pintype "bidirectional"))
    )
    (net (code "44") (name "unconnected-(IC1-(A14)PC6-Pad59)") (class "Default")
      (node (ref "IC1") (pin "59") (pinfunction "(A14)PC6_59") (pintype "bidirectional"))
    )
    (net (code "45") (name "unconnected-(IC1-(A15)PC7-Pad60)") (class "Default")
      (node (ref "IC1") (pin "60") (pinfunction "(A15)PC7_60") (pintype "bidirectional"))
    )
    (net (code "46") (name "unconnected-(IC1-(AD0)PA0-Pad78)") (class "Default")
      (node (ref "IC1") (pin "78") (pinfunction "(AD0)PA0_78") (pintype "bidirectional"))
    )
    (net (code "47") (name "unconnected-(IC1-(AD1)PA1-Pad77)") (class "Default")
      (node (ref "IC1") (pin "77") (pinfunction "(AD1)PA1_77") (pintype "bidirectional"))
    )
    (net (code "48") (name "unconnected-(IC1-(AD2)PA2-Pad76)") (class "Default")
      (node (ref "IC1") (pin "76") (pinfunction "(AD2)PA2_76") (pintype "bidirectional"))
    )
    (net (code "49") (name "unconnected-(IC1-(AD3)PA3-Pad75)") (class "Default")
      (node (ref "IC1") (pin "75") (pinfunction "(AD3)PA3_75") (pintype "bidirectional"))
    )
    (net (code "50") (name "unconnected-(IC1-(AD4)PA4-Pad74)") (class "Default")
      (node (ref "IC1") (pin "74") (pinfunction "(AD4)PA4_74") (pintype "bidirectional"))
    )
    (net (code "51") (name "unconnected-(IC1-(AD5)PA5-Pad73)") (class "Default")
      (node (ref "IC1") (pin "73") (pinfunction "(AD5)PA5_73") (pintype "bidirectional"))
    )
    (net (code "52") (name "unconnected-(IC1-(AD6)PA6-Pad72)") (class "Default")
      (node (ref "IC1") (pin "72") (pinfunction "(AD6)PA6_72") (pintype "bidirectional"))
    )
    (net (code "53") (name "unconnected-(IC1-(AD7)PA7-Pad71)") (class "Default")
      (node (ref "IC1") (pin "71") (pinfunction "(AD7)PA7_71") (pintype "bidirectional"))
    )
    (net (code "54") (name "unconnected-(IC1-(ADC0)PF0-Pad97)") (class "Default")
      (node (ref "IC1") (pin "97") (pinfunction "(ADC0)PF0_97") (pintype "bidirectional"))
    )
    (net (code "55") (name "unconnected-(IC1-(ADC1)PF1-Pad96)") (class "Default")
      (node (ref "IC1") (pin "96") (pinfunction "(ADC1)PF1_96") (pintype "bidirectional"))
    )
    (net (code "56") (name "unconnected-(IC1-(ADC2)PF2-Pad95)") (class "Default")
      (node (ref "IC1") (pin "95") (pinfunction "(ADC2)PF2_95") (pintype "bidirectional"))
    )
    (net (code "57") (name "unconnected-(IC1-(ADC3)PF3-Pad94)") (class "Default")
      (node (ref "IC1") (pin "94") (pinfunction "(ADC3)PF3_94") (pintype "bidirectional"))
    )
    (net (code "58") (name "unconnected-(IC1-(ADC4{slash}TCK)PF4-Pad93)") (class "Default")
      (node (ref "IC1") (pin "93") (pinfunction "(ADC4/TCK)PF4_93") (pintype "bidirectional"))
    )
    (net (code "59") (name "unconnected-(IC1-(ADC5{slash}TMS)PF5-Pad92)") (class "Default")
      (node (ref "IC1") (pin "92") (pinfunction "(ADC5/TMS)PF5_92") (pintype "bidirectional"))
    )
    (net (code "60") (name "unconnected-(IC1-(ADC6{slash}TDO)PF6-Pad91)") (class "Default")
      (node (ref "IC1") (pin "91") (pinfunction "(ADC6/TDO)PF6_91") (pintype "bidirectional"))
    )
    (net (code "61") (name "unconnected-(IC1-(ADC7{slash}TDI)PF7-Pad90)") (class "Default")
      (node (ref "IC1") (pin "90") (pinfunction "(ADC7/TDI)PF7_90") (pintype "bidirectional"))
    )
    (net (code "62") (name "unconnected-(IC1-(ALE)PG2-Pad70)") (class "Default")
      (node (ref "IC1") (pin "70") (pinfunction "(ALE)PG2_70") (pintype "bidirectional"))
    )
    (net (code "63") (name "unconnected-(IC1-(CLKO{slash}ICP3{slash}INT7)PE7-Pad9)") (class "Default")
      (node (ref "IC1") (pin "9") (pinfunction "(CLKO/ICP3/INT7)PE7_9") (pintype "bidirectional"))
    )
    (net (code "64") (name "unconnected-(IC1-(ICP1)PD4-Pad47)") (class "Default")
      (node (ref "IC1") (pin "47") (pinfunction "(ICP1)PD4_47") (pintype "bidirectional"))
    )
    (net (code "65") (name "unconnected-(IC1-(MISO{slash}PCINT3)PB3-Pad22)") (class "Default")
      (node (ref "IC1") (pin "22") (pinfunction "(MISO/PCINT3)PB3_22") (pintype "bidirectional"))
    )
    (net (code "66") (name "unconnected-(IC1-(MOSI{slash}PCINT2)PB2-Pad21)") (class "Default")
      (node (ref "IC1") (pin "21") (pinfunction "(MOSI/PCINT2)PB2_21") (pintype "bidirectional"))
    )
    (net (code "67") (name "unconnected-(IC1-(OC0A{slash}OC1C{slash}PCINT7)PB7-Pad26)") (class "Default")
      (node (ref "IC1") (pin "26") (pinfunction "(OC0A/OC1C/PCINT7)PB7_26") (pintype "bidirectional"))
    )
    (net (code "68") (name "unconnected-(IC1-(OC0B)PG5-Pad1)") (class "Default")
      (node (ref "IC1") (pin "1") (pinfunction "(OC0B)PG5_1") (pintype "bidirectional"))
    )
    (net (code "69") (name "unconnected-(IC1-(OC1A{slash}PCINT5)PB5-Pad24)") (class "Default")
      (node (ref "IC1") (pin "24") (pinfunction "(OC1A/PCINT5)PB5_24") (pintype "bidirectional"))
    )
    (net (code "70") (name "unconnected-(IC1-(OC1B{slash}PCINT6)PB6-Pad25)") (class "Default")
      (node (ref "IC1") (pin "25") (pinfunction "(OC1B/PCINT6)PB6_25") (pintype "bidirectional"))
    )
    (net (code "71") (name "unconnected-(IC1-(OC2A{slash}PCINT4)PB4-Pad23)") (class "Default")
      (node (ref "IC1") (pin "23") (pinfunction "(OC2A/PCINT4)PB4_23") (pintype "bidirectional"))
    )
    (net (code "72") (name "unconnected-(IC1-(OC3A{slash}AIN1)PE3-Pad5)") (class "Default")
      (node (ref "IC1") (pin "5") (pinfunction "(OC3A/AIN1)PE3_5") (pintype "bidirectional"))
    )
    (net (code "73") (name "unconnected-(IC1-(OC3B{slash}INT4)PE4-Pad6)") (class "Default")
      (node (ref "IC1") (pin "6") (pinfunction "(OC3B/INT4)PE4_6") (pintype "bidirectional"))
    )
    (net (code "74") (name "unconnected-(IC1-(OC3C{slash}INT5)PE5-Pad7)") (class "Default")
      (node (ref "IC1") (pin "7") (pinfunction "(OC3C/INT5)PE5_7") (pintype "bidirectional"))
    )
    (net (code "75") (name "unconnected-(IC1-(RD)PG1-Pad52)") (class "Default")
      (node (ref "IC1") (pin "52") (pinfunction "(RD)PG1_52") (pintype "bidirectional"))
    )
    (net (code "76") (name "unconnected-(IC1-(SCK{slash}PCINT1)PB1-Pad20)") (class "Default")
      (node (ref "IC1") (pin "20") (pinfunction "(SCK/PCINT1)PB1_20") (pintype "bidirectional"))
    )
    (net (code "77") (name "unconnected-(IC1-(SCL{slash}INT0)PD0-Pad43)") (class "Default")
      (node (ref "IC1") (pin "43") (pinfunction "(SCL/INT0)PD0_43") (pintype "bidirectional"))
    )
    (net (code "78") (name "unconnected-(IC1-(SDA{slash}INT1)PD1-Pad44)") (class "Default")
      (node (ref "IC1") (pin "44") (pinfunction "(SDA/INT1)PD1_44") (pintype "bidirectional"))
    )
    (net (code "79") (name "unconnected-(IC1-(SS{slash}PCINT0)PB0-Pad19)") (class "Default")
      (node (ref "IC1") (pin "19") (pinfunction "(SS/PCINT0)PB0_19") (pintype "bidirectional"))
    )
    (net (code "80") (name "unconnected-(IC1-(T0)PD7-Pad50)") (class "Default")
      (node (ref "IC1") (pin "50") (pinfunction "(T0)PD7_50") (pintype "bidirectional"))
    )
    (net (code "81") (name "unconnected-(IC1-(T1)PD6-Pad49)") (class "Default")
      (node (ref "IC1") (pin "49") (pinfunction "(T1)PD6_49") (pintype "bidirectional"))
    )
    (net (code "82") (name "unconnected-(IC1-(T3{slash}INT6)PE6-Pad8)") (class "Default")
      (node (ref "IC1") (pin "8") (pinfunction "(T3/INT6)PE6_8") (pintype "bidirectional"))
    )
    (net (code "83") (name "unconnected-(IC1-(TOSC1)PG4-Pad29)") (class "Default")
      (node (ref "IC1") (pin "29") (pinfunction "(TOSC1)PG4_29") (pintype "bidirectional"))
    )
    (net (code "84") (name "unconnected-(IC1-(TOSC2)PG3-Pad28)") (class "Default")
      (node (ref "IC1") (pin "28") (pinfunction "(TOSC2)PG3_28") (pintype "bidirectional"))
    )
    (net (code "85") (name "unconnected-(IC1-(WR)PG0-Pad51)") (class "Default")
      (node (ref "IC1") (pin "51") (pinfunction "(WR)PG0_51") (pintype "bidirectional"))
    )
    (net (code "86") (name "unconnected-(IC1-(XCK0{slash}AIN0)PE2-Pad4)") (class "Default")
      (node (ref "IC1") (pin "4") (pinfunction "(XCK0/AIN0)PE2_4") (pintype "bidirectional"))
    )
    (net (code "87") (name "unconnected-(IC1-(XCK1)PD5-Pad48)") (class "Default")
      (node (ref "IC1") (pin "48") (pinfunction "(XCK1)PD5_48") (pintype "bidirectional"))
    )
    (net (code "88") (name "unconnected-(IC1-PH2(XCK2)-Pad14)") (class "Default")
      (node (ref "IC1") (pin "14") (pinfunction "PH2(XCK2)_14") (pintype "bidirectional"))
    )
    (net (code "89") (name "unconnected-(IC1-PH3(OC4A)-Pad15)") (class "Default")
      (node (ref "IC1") (pin "15") (pinfunction "PH3(OC4A)_15") (pintype "bidirectional"))
    )
    (net (code "90") (name "unconnected-(IC1-PH4(OC4B)-Pad16)") (class "Default")
      (node (ref "IC1") (pin "16") (pinfunction "PH4(OC4B)_16") (pintype "bidirectional"))
    )
    (net (code "91") (name "unconnected-(IC1-PH5(OC4C)-Pad17)") (class "Default")
      (node (ref "IC1") (pin "17") (pinfunction "PH5(OC4C)_17") (pintype "bidirectional"))
    )
    (net (code "92") (name "unconnected-(IC1-PH6(OC2B)-Pad18)") (class "Default")
      (node (ref "IC1") (pin "18") (pinfunction "PH6(OC2B)_18") (pintype "bidirectional"))
    )
    (net (code "93") (name "unconnected-(IC1-PH7(T4)-Pad27)") (class "Default")
      (node (ref "IC1") (pin "27") (pinfunction "PH7(T4)_27") (pintype "bidirectional"))
    )
    (net (code "94") (name "unconnected-(IC1-PJ2(XCK3{slash}PCINT11)-Pad65)") (class "Default")
      (node (ref "IC1") (pin "65") (pinfunction "PJ2(XCK3/PCINT11)_65") (pintype "bidirectional"))
    )
    (net (code "95") (name "unconnected-(IC1-PJ3(PCINT12)-Pad66)") (class "Default")
      (node (ref "IC1") (pin "66") (pinfunction "PJ3(PCINT12)_66") (pintype "bidirectional"))
    )
    (net (code "96") (name "unconnected-(IC1-PJ4(PCINT13)-Pad67)") (class "Default")
      (node (ref "IC1") (pin "67") (pinfunction "PJ4(PCINT13)_67") (pintype "bidirectional"))
    )
    (net (code "97") (name "unconnected-(IC1-PJ5(PCINT14)-Pad68)") (class "Default")
      (node (ref "IC1") (pin "68") (pinfunction "PJ5(PCINT14)_68") (pintype "bidirectional"))
    )
    (net (code "98") (name "unconnected-(IC1-PJ6(PCINT15)-Pad69)") (class "Default")
      (node (ref "IC1") (pin "69") (pinfunction "PJ6(PCINT15)_69") (pintype "bidirectional"))
    )
    (net (code "99") (name "unconnected-(IC1-PJ7-Pad79)") (class "Default")
      (node (ref "IC1") (pin "79") (pinfunction "PJ7_79") (pintype "bidirectional"))
    )
    (net (code "100") (name "unconnected-(IC1-PK0(ADC8{slash}PCINT16)-Pad89)") (class "Default")
      (node (ref "IC1") (pin "89") (pinfunction "PK0(ADC8/PCINT16)_89") (pintype "bidirectional"))
    )
    (net (code "101") (name "unconnected-(IC1-PK1(ADC9{slash}PCINT17)-Pad88)") (class "Default")
      (node (ref "IC1") (pin "88") (pinfunction "PK1(ADC9/PCINT17)_88") (pintype "bidirectional"))
    )
    (net (code "102") (name "unconnected-(IC1-PK2(ADC10{slash}PCINT18)-Pad87)") (class "Default")
      (node (ref "IC1") (pin "87") (pinfunction "PK2(ADC10/PCINT18)_87") (pintype "bidirectional"))
    )
    (net (code "103") (name "unconnected-(IC1-PK3(ADC11{slash}PCINT19)-Pad86)") (class "Default")
      (node (ref "IC1") (pin "86") (pinfunction "PK3(ADC11/PCINT19)_86") (pintype "bidirectional"))
    )
    (net (code "104") (name "unconnected-(IC1-PK4(ADC12{slash}PCINT20)-Pad85)") (class "Default")
      (node (ref "IC1") (pin "85") (pinfunction "PK4(ADC12/PCINT20)_85") (pintype "bidirectional"))
    )
    (net (code "105") (name "unconnected-(IC1-PK5(ADC13{slash}PCINT21)-Pad84)") (class "Default")
      (node (ref "IC1") (pin "84") (pinfunction "PK5(ADC13/PCINT21)_84") (pintype "bidirectional"))
    )
    (net (code "106") (name "unconnected-(IC1-PK6(ADC14{slash}PCINT22)-Pad83)") (class "Default")
      (node (ref "IC1") (pin "83") (pinfunction "PK6(ADC14/PCINT22)_83") (pintype "bidirectional"))
    )
    (net (code "107") (name "unconnected-(IC1-PK7(ADC15{slash}PCINT23)-Pad82)") (class "Default")
      (node (ref "IC1") (pin "82") (pinfunction "PK7(ADC15/PCINT23)_82") (pintype "bidirectional"))
    )
    (net (code "108") (name "unconnected-(IC1-PL0(ICP4)-Pad35)") (class "Default")
      (node (ref "IC1") (pin "35") (pinfunction "PL0(ICP4)_35") (pintype "bidirectional"))
    )
    (net (code "109") (name "unconnected-(IC1-PL1(ICP5)-Pad36)") (class "Default")
      (node (ref "IC1") (pin "36") (pinfunction "PL1(ICP5)_36") (pintype "bidirectional"))
    )
    (net (code "110") (name "unconnected-(LRW-RN2903-GPIO0-Pad35)") (class "Default")
      (node (ref "LRW-RN2903") (pin "35") (pinfunction "GPIO0_35") (pintype "bidirectional"))
    )
    (net (code "111") (name "unconnected-(LRW-RN2903-GPIO1-Pad36)") (class "Default")
      (node (ref "LRW-RN2903") (pin "36") (pinfunction "GPIO1_36") (pintype "bidirectional"))
    )
    (net (code "112") (name "unconnected-(LRW-RN2903-GPIO2-Pad37)") (class "Default")
      (node (ref "LRW-RN2903") (pin "37") (pinfunction "GPIO2_37") (pintype "bidirectional"))
    )
    (net (code "113") (name "unconnected-(LRW-RN2903-GPIO3-Pad38)") (class "Default")
      (node (ref "LRW-RN2903") (pin "38") (pinfunction "GPIO3_38") (pintype "bidirectional"))
    )
    (net (code "114") (name "unconnected-(LRW-RN2903-GPIO4-Pad39)") (class "Default")
      (node (ref "LRW-RN2903") (pin "39") (pinfunction "GPIO4_39") (pintype "bidirectional"))
    )
    (net (code "115") (name "unconnected-(LRW-RN2903-GPIO5-Pad40)") (class "Default")
      (node (ref "LRW-RN2903") (pin "40") (pinfunction "GPIO5_40") (pintype "bidirectional"))
    )
    (net (code "116") (name "unconnected-(LRW-RN2903-GPIO6-Pad43)") (class "Default")
      (node (ref "LRW-RN2903") (pin "43") (pinfunction "GPIO6_43") (pintype "bidirectional"))
    )
    (net (code "117") (name "unconnected-(LRW-RN2903-GPIO7-Pad44)") (class "Default")
      (node (ref "LRW-RN2903") (pin "44") (pinfunction "GPIO7_44") (pintype "bidirectional"))
    )
    (net (code "118") (name "unconnected-(LRW-RN2903-GPIO8-Pad45)") (class "Default")
      (node (ref "LRW-RN2903") (pin "45") (pinfunction "GPIO8_45") (pintype "bidirectional"))
    )
    (net (code "119") (name "unconnected-(LRW-RN2903-GPIO9-Pad46)") (class "Default")
      (node (ref "LRW-RN2903") (pin "46") (pinfunction "GPIO9_46") (pintype "bidirectional"))
    )
    (net (code "120") (name "unconnected-(LRW-RN2903-GPIO10-Pad14)") (class "Default")
      (node (ref "LRW-RN2903") (pin "14") (pinfunction "GPIO10_14") (pintype "bidirectional"))
    )
    (net (code "121") (name "unconnected-(LRW-RN2903-GPIO11-Pad13)") (class "Default")
      (node (ref "LRW-RN2903") (pin "13") (pinfunction "GPIO11_13") (pintype "bidirectional"))
    )
    (net (code "122") (name "unconnected-(LRW-RN2903-GPIO12-Pad10)") (class "Default")
      (node (ref "LRW-RN2903") (pin "10") (pinfunction "GPIO12_10") (pintype "bidirectional"))
    )
    (net (code "123") (name "unconnected-(LRW-RN2903-GPIO13-Pad9)") (class "Default")
      (node (ref "LRW-RN2903") (pin "9") (pinfunction "GPIO13_9") (pintype "bidirectional"))
    )
    (net (code "124") (name "unconnected-(LRW-RN2903-NC-Pad15)") (class "Default")
      (node (ref "LRW-RN2903") (pin "15") (pinfunction "NC_15") (pintype "no_connect"))
    )
    (net (code "125") (name "unconnected-(LRW-RN2903-NC-Pad16)") (class "Default")
      (node (ref "LRW-RN2903") (pin "16") (pinfunction "NC_16") (pintype "no_connect"))
    )
    (net (code "126") (name "unconnected-(LRW-RN2903-NC-Pad17)") (class "Default")
      (node (ref "LRW-RN2903") (pin "17") (pinfunction "NC_17") (pintype "no_connect"))
    )
    (net (code "127") (name "unconnected-(LRW-RN2903-NC-Pad18)") (class "Default")
      (node (ref "LRW-RN2903") (pin "18") (pinfunction "NC_18") (pintype "no_connect"))
    )
    (net (code "128") (name "unconnected-(LRW-RN2903-NC-Pad19)") (class "Default")
      (node (ref "LRW-RN2903") (pin "19") (pinfunction "NC_19") (pintype "no_connect"))
    )
    (net (code "129") (name "unconnected-(LRW-RN2903-NC-Pad29)") (class "Default")
      (node (ref "LRW-RN2903") (pin "29") (pinfunction "NC_29") (pintype "no_connect"))
    )
    (net (code "130") (name "unconnected-(LRW-RN2903-NC-Pad42)") (class "Default")
      (node (ref "LRW-RN2903") (pin "42") (pinfunction "NC_42") (pintype "no_connect"))
    )
    (net (code "131") (name "unconnected-(LRW-RN2903-PGC_INT-Pad30)") (class "Default")
      (node (ref "LRW-RN2903") (pin "30") (pinfunction "PGC_INT_30") (pintype "bidirectional"))
    )
    (net (code "132") (name "unconnected-(LRW-RN2903-PGD_INT-Pad31)") (class "Default")
      (node (ref "LRW-RN2903") (pin "31") (pinfunction "PGD_INT_31") (pintype "bidirectional"))
    )
    (net (code "133") (name "unconnected-(LRW-RN2903-RESERVED-Pad4)") (class "Default")
      (node (ref "LRW-RN2903") (pin "4") (pinfunction "RESERVED_4") (pintype "no_connect"))
    )
    (net (code "134") (name "unconnected-(LRW-RN2903-RESERVED-Pad5)") (class "Default")
      (node (ref "LRW-RN2903") (pin "5") (pinfunction "RESERVED_5") (pintype "no_connect"))
    )
    (net (code "135") (name "unconnected-(LRW-RN2903-RFL-Pad25)") (class "Default")
      (node (ref "LRW-RN2903") (pin "25") (pinfunction "RFL_25") (pintype "bidirectional"))
    )
    (net (code "136") (name "unconnected-(LRW-RN2903-UART_CTS-Pad3)") (class "Default")
      (node (ref "LRW-RN2903") (pin "3") (pinfunction "UART_CTS_3") (pintype "input"))
    )
    (net (code "137") (name "unconnected-(LRW-RN2903-UART_RTS-Pad2)") (class "Default")
      (node (ref "LRW-RN2903") (pin "2") (pinfunction "UART_RTS_2") (pintype "output"))
    )
    (net (code "138") (name "unconnected-(USB-SERIAL-Pad1)") (class "Default")
      (node (ref "USB-SERIAL") (pin "1") (pinfunction "1_1") (pintype "passive"))
    )
  )
)
